# Washer_Control_Board.net
KiCad netlist of a schematic drawn in EAGLE
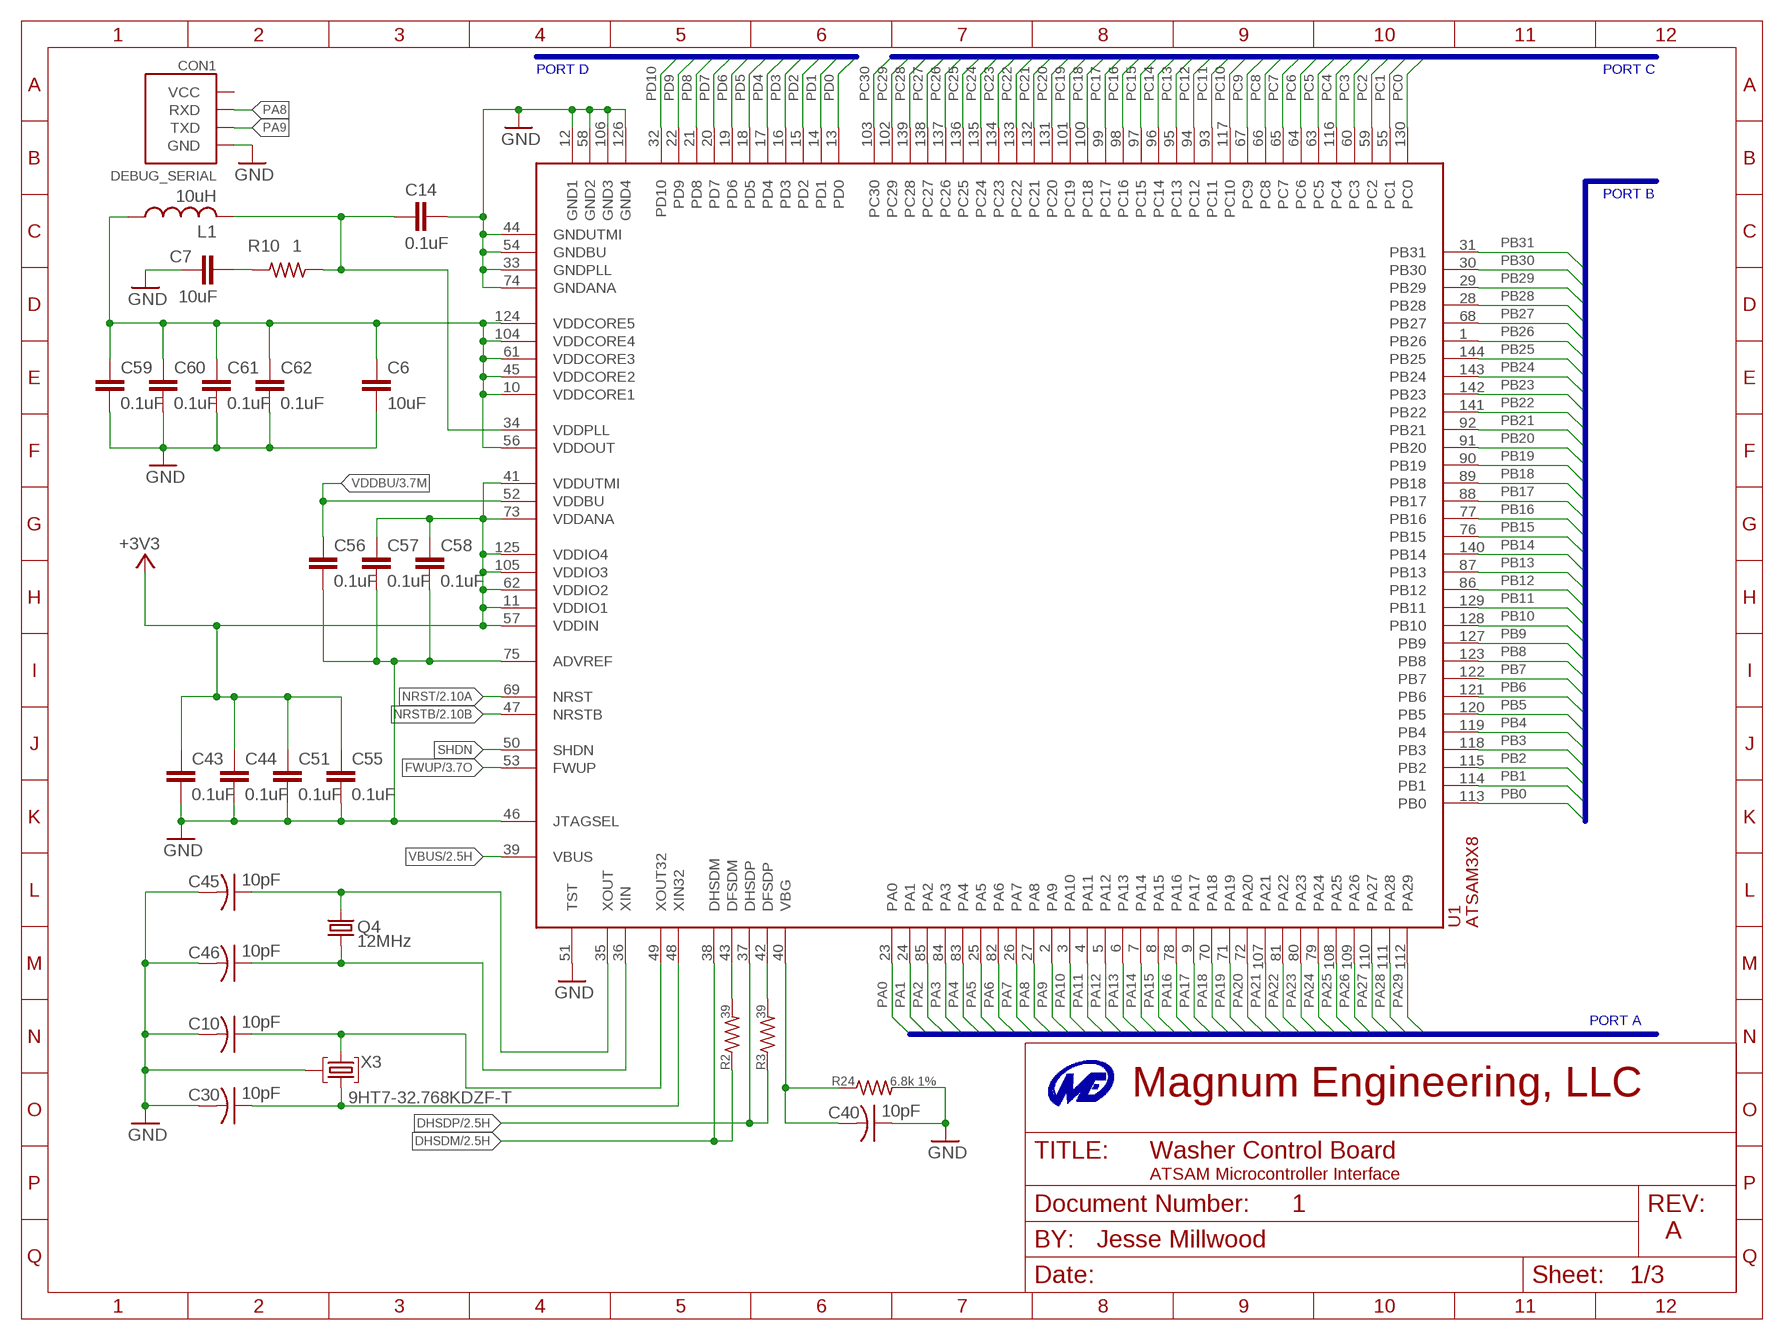
[diagram p0: schematic, sheet 1]
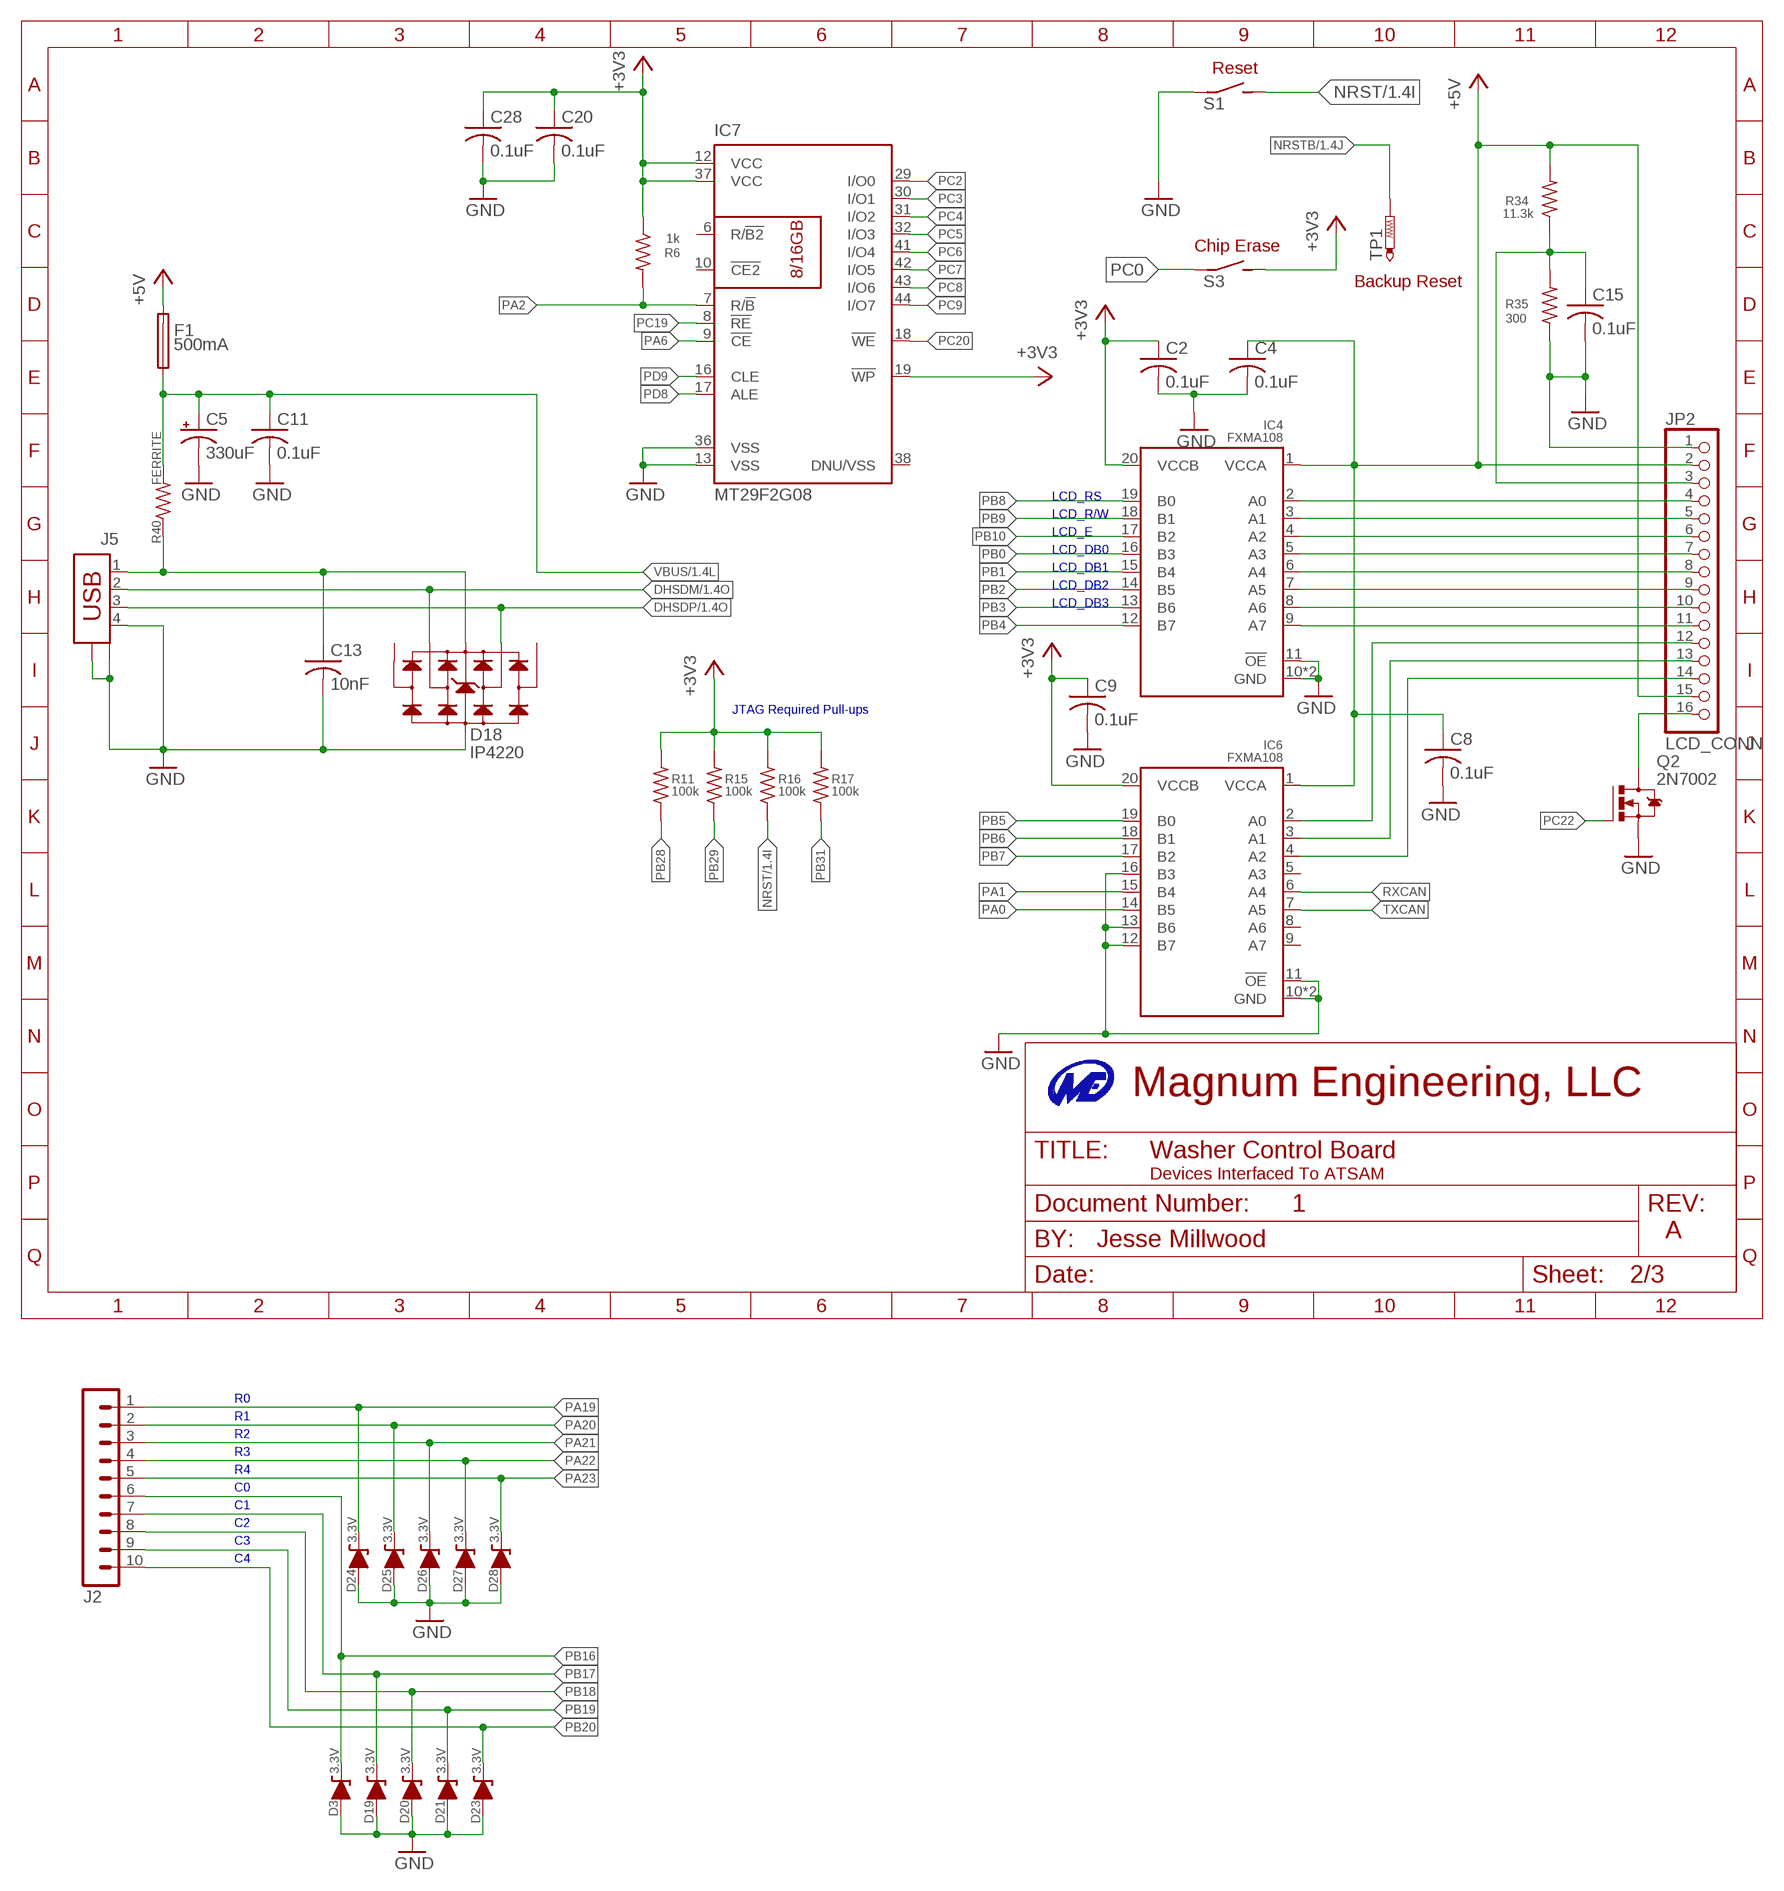
[diagram p1: schematic, sheet 2]
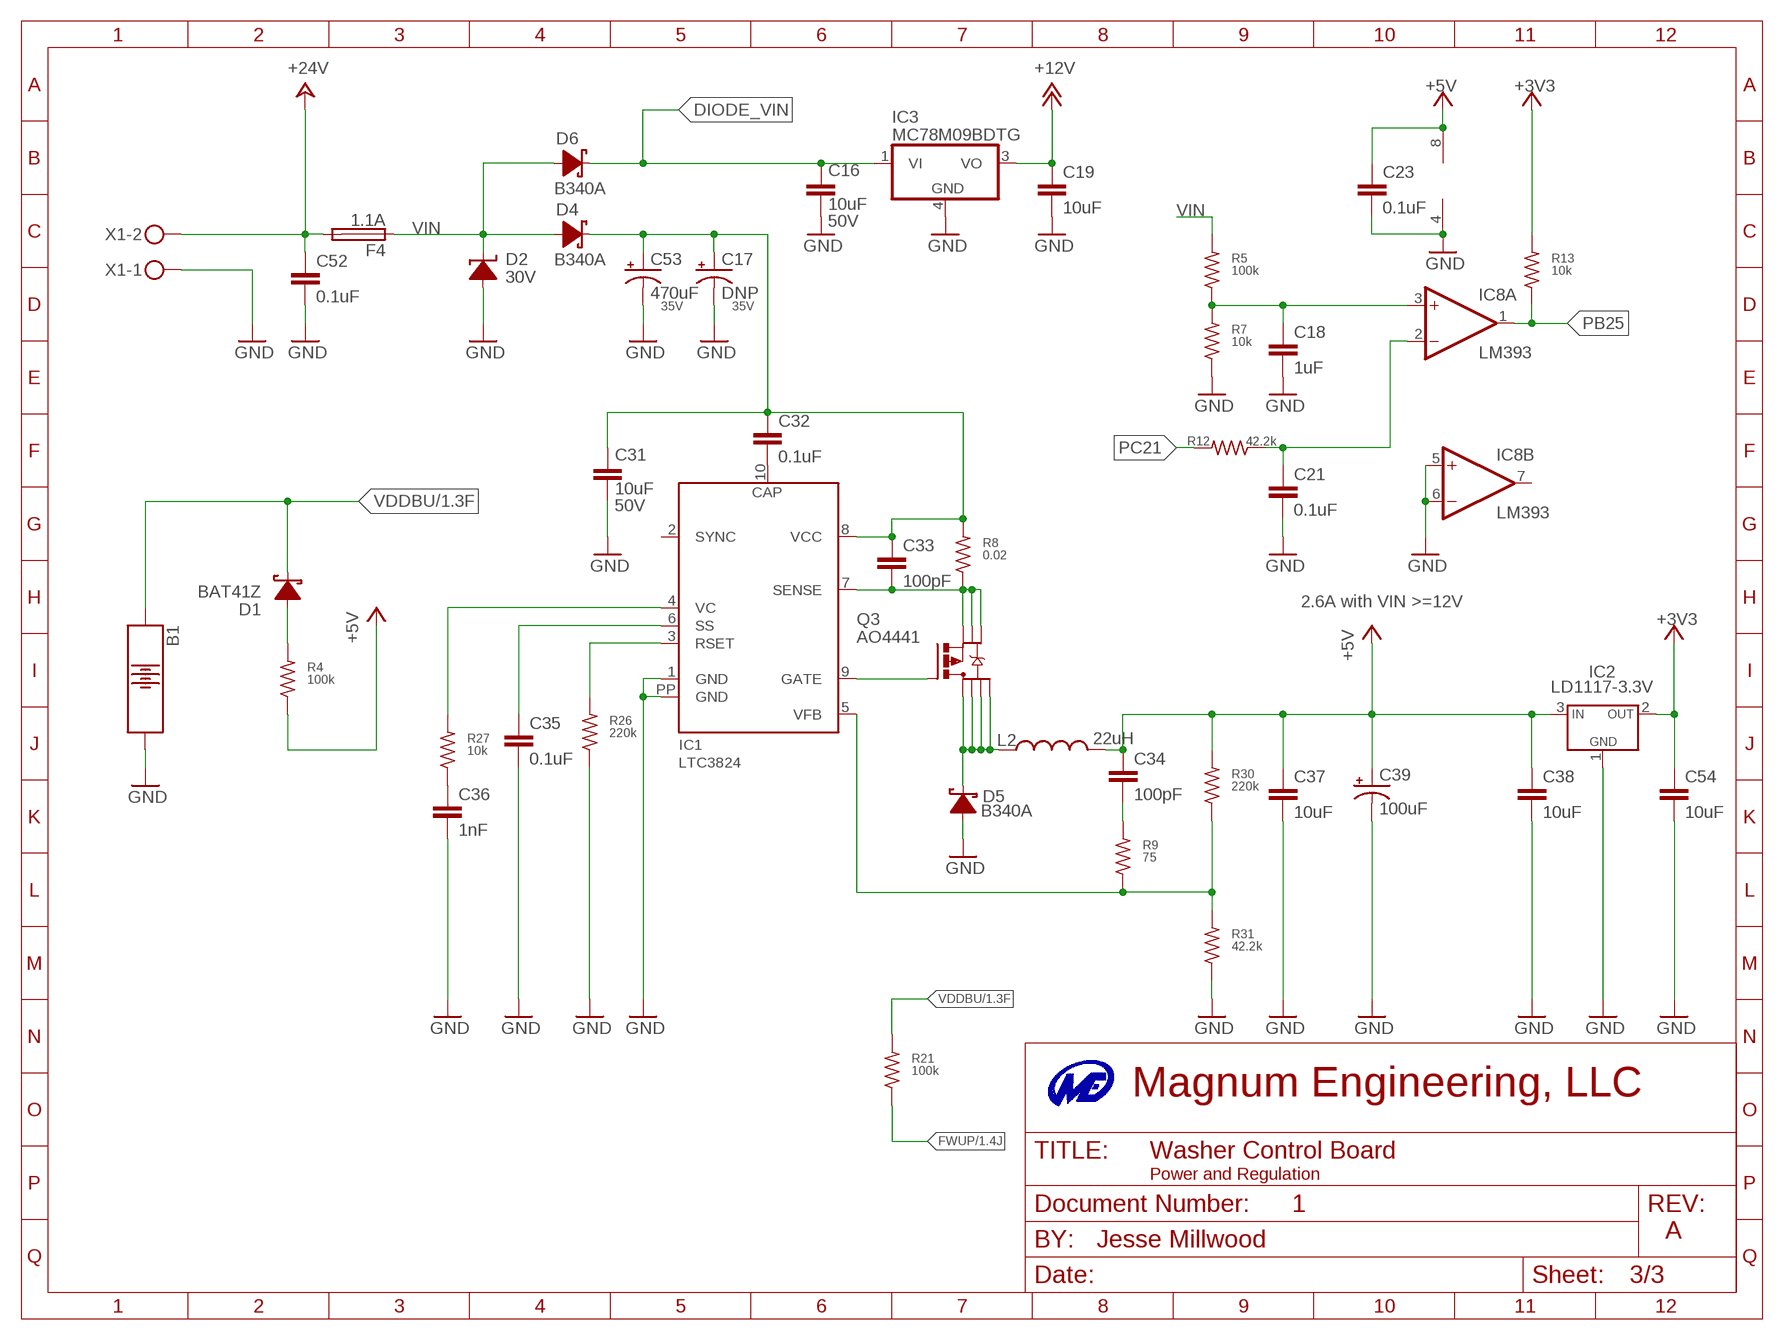
[diagram p2: schematic, sheet 3]

(export (version "E")
  (design (tool "Eeschema 10.0.6"))
  (components
    (comp (ref "C6")
      (value "10uF")
      (footprint "eagle-import:C0805")
      (libsource (lib "eagle-import") (part "C-EUC0805"))
    )
    (comp (ref "C7")
      (value "10uF")
      (footprint "eagle-import:C0805")
      (libsource (lib "eagle-import") (part "C-EUC0805"))
    )
    (comp (ref "C10")
      (value "10pF")
      (footprint "eagle-import:C0805")
      (libsource (lib "eagle-import") (part "CAPACITOR0805"))
    )
    (comp (ref "C14")
      (value "0.1uF")
      (footprint "eagle-import:C0805")
      (libsource (lib "eagle-import") (part "C-EUC0805"))
    )
    (comp (ref "C30")
      (value "10pF")
      (footprint "eagle-import:C0805")
      (libsource (lib "eagle-import") (part "CAPACITOR0805"))
    )
    (comp (ref "C40")
      (value "10pF")
      (footprint "eagle-import:C0805")
      (libsource (lib "eagle-import") (part "CAPACITOR0805"))
    )
    (comp (ref "C43")
      (value "0.1uF")
      (footprint "eagle-import:C0805")
      (libsource (lib "eagle-import") (part "C-EUC0805"))
    )
    (comp (ref "C44")
      (value "0.1uF")
      (footprint "eagle-import:C0805")
      (libsource (lib "eagle-import") (part "C-EUC0805"))
    )
    (comp (ref "C45")
      (value "10pF")
      (footprint "eagle-import:C0805")
      (libsource (lib "eagle-import") (part "CAPACITOR0805"))
    )
    (comp (ref "C46")
      (value "10pF")
      (footprint "eagle-import:C0805")
      (libsource (lib "eagle-import") (part "CAPACITOR0805"))
    )
    (comp (ref "C51")
      (value "0.1uF")
      (footprint "eagle-import:C0805")
      (libsource (lib "eagle-import") (part "C-EUC0805"))
    )
    (comp (ref "C55")
      (value "0.1uF")
      (footprint "eagle-import:C0805")
      (libsource (lib "eagle-import") (part "C-EUC0805"))
    )
    (comp (ref "C56")
      (value "0.1uF")
      (footprint "eagle-import:C0805")
      (libsource (lib "eagle-import") (part "C-EUC0805"))
    )
    (comp (ref "C57")
      (value "0.1uF")
      (footprint "eagle-import:C0805")
      (libsource (lib "eagle-import") (part "C-EUC0805"))
    )
    (comp (ref "C58")
      (value "0.1uF")
      (footprint "eagle-import:C0805")
      (libsource (lib "eagle-import") (part "C-EUC0805"))
    )
    (comp (ref "C59")
      (value "0.1uF")
      (footprint "eagle-import:C0805")
      (libsource (lib "eagle-import") (part "C-EUC0805"))
    )
    (comp (ref "C60")
      (value "0.1uF")
      (footprint "eagle-import:C0805")
      (libsource (lib "eagle-import") (part "C-EUC0805"))
    )
    (comp (ref "C61")
      (value "0.1uF")
      (footprint "eagle-import:C0805")
      (libsource (lib "eagle-import") (part "C-EUC0805"))
    )
    (comp (ref "C62")
      (value "0.1uF")
      (footprint "eagle-import:C0805")
      (libsource (lib "eagle-import") (part "C-EUC0805"))
    )
    (comp (ref "CON1")
      (value "DEBUG_SERIAL")
      (footprint "eagle-import:VIDEO_PARTS_DEBUG_SERIAL")
      (libsource (lib "eagle-import") (part "VIDEO_PARTS_DEBUG_SERIAL"))
    )
    (comp (ref "L1")
      (value "10uH")
      (footprint "eagle-import:L2012C")
      (libsource (lib "eagle-import") (part "rcl_L-USL2012C"))
    )
    (comp (ref "Q4")
      (value "12MHz")
      (footprint "eagle-import:HC49UP")
      (libsource (lib "eagle-import") (part "CRYSTALHC49UP"))
    )
    (comp (ref "R2")
      (value "39")
      (footprint "eagle-import:R0805")
      (libsource (lib "eagle-import") (part "RESISTOR0805"))
    )
    (comp (ref "R3")
      (value "39")
      (footprint "eagle-import:R0805")
      (libsource (lib "eagle-import") (part "RESISTOR0805"))
    )
    (comp (ref "R10")
      (value "1")
      (footprint "eagle-import:R0805")
      (libsource (lib "eagle-import") (part "R-US_R0805"))
    )
    (comp (ref "R24")
      (value "6.8k 1%")
      (footprint "eagle-import:R0805")
      (libsource (lib "eagle-import") (part "RESISTOR0805"))
    )
    (comp (ref "U1")
      (value "ATSAM3X8")
      (footprint "eagle-import:SMARTPRJ_LQFP144")
      (libsource (lib "eagle-import") (part "SMARTPRJ_ATSAM3X/AAU"))
    )
    (comp (ref "X3")
      (value "9HT7-32.768KDZF-T")
      (footprint "eagle-import:TXC-9HT7")
      (libsource (lib "eagle-import") (part "CRYSTAL"))
    )
    (comp (ref "C2")
      (value "0.1uF")
      (footprint "eagle-import:C0805")
      (libsource (lib "eagle-import") (part "CAPACITOR0805"))
    )
    (comp (ref "C4")
      (value "0.1uF")
      (footprint "eagle-import:C0805")
      (libsource (lib "eagle-import") (part "CAPACITOR0805"))
    )
    (comp (ref "C5")
      (value "330uF")
      (footprint "eagle-import:E2,5-6")
      (libsource (lib "eagle-import") (part "CPOL-USE2.5-6"))
    )
    (comp (ref "C8")
      (value "0.1uF")
      (footprint "eagle-import:C0805")
      (libsource (lib "eagle-import") (part "CAPACITOR0805"))
    )
    (comp (ref "C9")
      (value "0.1uF")
      (footprint "eagle-import:C0805")
      (libsource (lib "eagle-import") (part "CAPACITOR0805"))
    )
    (comp (ref "C11")
      (value "0.1uF")
      (footprint "eagle-import:C0805")
      (libsource (lib "eagle-import") (part "CAPACITOR0805"))
    )
    (comp (ref "C13")
      (value "10nF")
      (footprint "eagle-import:C0805")
      (libsource (lib "eagle-import") (part "CAPACITOR0805"))
    )
    (comp (ref "C15")
      (value "0.1uF")
      (footprint "eagle-import:C0805")
      (libsource (lib "eagle-import") (part "CAPACITOR0805"))
    )
    (comp (ref "C20")
      (value "0.1uF")
      (footprint "eagle-import:C0805")
      (libsource (lib "eagle-import") (part "CAPACITOR0805"))
    )
    (comp (ref "C28")
      (value "0.1uF")
      (footprint "eagle-import:C0805")
      (libsource (lib "eagle-import") (part "CAPACITOR0805"))
    )
    (comp (ref "D3")
      (value "3.3V")
      (footprint "eagle-import:SOT-23")
      (libsource (lib "eagle-import") (part "ZENERSOT-23"))
    )
    (comp (ref "D18")
      (value "IP4220")
      (footprint "eagle-import:SOT-23-6")
      (libsource (lib "eagle-import") (part "IP4220"))
    )
    (comp (ref "D19")
      (value "3.3V")
      (footprint "eagle-import:SOT-23")
      (libsource (lib "eagle-import") (part "ZENERSOT-23"))
    )
    (comp (ref "D20")
      (value "3.3V")
      (footprint "eagle-import:SOT-23")
      (libsource (lib "eagle-import") (part "ZENERSOT-23"))
    )
    (comp (ref "D21")
      (value "3.3V")
      (footprint "eagle-import:SOT-23")
      (libsource (lib "eagle-import") (part "ZENERSOT-23"))
    )
    (comp (ref "D23")
      (value "3.3V")
      (footprint "eagle-import:SOT-23")
      (libsource (lib "eagle-import") (part "ZENERSOT-23"))
    )
    (comp (ref "D24")
      (value "3.3V")
      (footprint "eagle-import:SOT-23")
      (libsource (lib "eagle-import") (part "ZENERSOT-23"))
    )
    (comp (ref "D25")
      (value "3.3V")
      (footprint "eagle-import:SOT-23")
      (libsource (lib "eagle-import") (part "ZENERSOT-23"))
    )
    (comp (ref "D26")
      (value "3.3V")
      (footprint "eagle-import:SOT-23")
      (libsource (lib "eagle-import") (part "ZENERSOT-23"))
    )
    (comp (ref "D27")
      (value "3.3V")
      (footprint "eagle-import:SOT-23")
      (libsource (lib "eagle-import") (part "ZENERSOT-23"))
    )
    (comp (ref "D28")
      (value "3.3V")
      (footprint "eagle-import:SOT-23")
      (libsource (lib "eagle-import") (part "ZENERSOT-23"))
    )
    (comp (ref "F1")
      (value "500mA")
      (footprint "eagle-import:LITTELFUSE1812")
      (libsource (lib "eagle-import") (part "ads4_FUSELITTELFUSE1812"))
    )
    (comp (ref "IC4")
      (value "FXMA108")
      (footprint "eagle-import:20DQFN")
      (libsource (lib "eagle-import") (part "FXMA108"))
    )
    (comp (ref "IC6")
      (value "FXMA108")
      (footprint "eagle-import:20DQFN")
      (libsource (lib "eagle-import") (part "FXMA108"))
    )
    (comp (ref "IC7")
      (value "MT29F2G08")
      (footprint "eagle-import:TSOP48")
      (libsource (lib "eagle-import") (part "MT29F8G08DAA"))
    )
    (comp (ref "J2")
      (value "MA10-152271")
      (footprint "eagle-import:52271-1069")
      (libsource (lib "eagle-import") (part "MA10-152271"))
    )
    (comp (ref "J5")
      (value "USB-787616")
      (footprint "eagle-import:USB")
      (libsource (lib "eagle-import") (part "USB-787616"))
    )
    (comp (ref "JP2")
      (value "LCD_CONN")
      (footprint "eagle-import:1X16")
      (libsource (lib "eagle-import") (part "PINHD-1X16"))
    )
    (comp (ref "Q2")
      (value "2N7002")
      (footprint "eagle-import:SOT-23")
      (libsource (lib "eagle-import") (part "2N7002"))
    )
    (comp (ref "R6")
      (value "1k")
      (footprint "eagle-import:R0805")
      (libsource (lib "eagle-import") (part "R-US_R0805"))
    )
    (comp (ref "R11")
      (value "100k")
      (footprint "eagle-import:R0805")
      (libsource (lib "eagle-import") (part "RESISTOR0805"))
    )
    (comp (ref "R15")
      (value "100k")
      (footprint "eagle-import:R0805")
      (libsource (lib "eagle-import") (part "RESISTOR0805"))
    )
    (comp (ref "R16")
      (value "100k")
      (footprint "eagle-import:R0805")
      (libsource (lib "eagle-import") (part "RESISTOR0805"))
    )
    (comp (ref "R17")
      (value "100k")
      (footprint "eagle-import:R0805")
      (libsource (lib "eagle-import") (part "RESISTOR0805"))
    )
    (comp (ref "R34")
      (value "11.3k")
      (footprint "eagle-import:R0805")
      (libsource (lib "eagle-import") (part "R-US_R0805"))
    )
    (comp (ref "R35")
      (value "300")
      (footprint "eagle-import:R0805")
      (libsource (lib "eagle-import") (part "R-US_R0805"))
    )
    (comp (ref "R40")
      (value "FERRITE")
      (footprint "eagle-import:R0805")
      (libsource (lib "eagle-import") (part "RESISTOR0805"))
    )
    (comp (ref "S1")
      (value "Reset")
      (footprint "eagle-import:EVQPJ")
      (libsource (lib "eagle-import") (part "SPST2EVQPJ"))
    )
    (comp (ref "S3")
      (value "Chip Erase")
      (footprint "eagle-import:EVQPJ")
      (libsource (lib "eagle-import") (part "SPST2EVQPJ"))
    )
    (comp (ref "TP1")
      (value "PTR1TP06R")
      (footprint "eagle-import:TP06R")
      (libsource (lib "eagle-import") (part "PTR1TP06R"))
    )
    (comp (ref "B1")
      (value "BS-7-ND")
      (footprint "eagle-import:BS-7-BATTERY-HOLDER")
      (libsource (lib "eagle-import") (part "BS-7-ND"))
    )
    (comp (ref "C16")
      (value "10uF")
      (footprint "eagle-import:C1206")
      (fields (field (name "VOLTAGE") "50V"))
      (libsource (lib "eagle-import") (part "C-EUC1206"))
    )
    (comp (ref "C17")
      (value "DNP")
      (footprint "eagle-import:RCL_E5-10,5")
      (fields (field (name "VOLTAGE") "35V"))
      (libsource (lib "eagle-import") (part "POL-CAPACITOR5-10.5"))
    )
    (comp (ref "C18")
      (value "1uF")
      (footprint "eagle-import:C0805")
      (libsource (lib "eagle-import") (part "C-EUC0805"))
    )
    (comp (ref "C19")
      (value "10uF")
      (footprint "eagle-import:C0805")
      (libsource (lib "eagle-import") (part "C-EUC0805"))
    )
    (comp (ref "C21")
      (value "0.1uF")
      (footprint "eagle-import:C0805")
      (libsource (lib "eagle-import") (part "C-EUC0805"))
    )
    (comp (ref "C23")
      (value "0.1uF")
      (footprint "eagle-import:C0805")
      (libsource (lib "eagle-import") (part "C-EUC0805"))
    )
    (comp (ref "C31")
      (value "10uF")
      (footprint "eagle-import:C1206")
      (fields (field (name "VOLTAGE") "50V"))
      (libsource (lib "eagle-import") (part "C-EUC1206"))
    )
    (comp (ref "C32")
      (value "0.1uF")
      (footprint "eagle-import:C0805")
      (libsource (lib "eagle-import") (part "C-EUC0805"))
    )
    (comp (ref "C33")
      (value "100pF")
      (footprint "eagle-import:C0805")
      (libsource (lib "eagle-import") (part "C-EUC0805"))
    )
    (comp (ref "C34")
      (value "100pF")
      (footprint "eagle-import:C0805")
      (libsource (lib "eagle-import") (part "C-EUC0805"))
    )
    (comp (ref "C35")
      (value "0.1uF")
      (footprint "eagle-import:C0805")
      (libsource (lib "eagle-import") (part "C-EUC0805"))
    )
    (comp (ref "C36")
      (value "1nF")
      (footprint "eagle-import:C0805")
      (libsource (lib "eagle-import") (part "C-EUC0805"))
    )
    (comp (ref "C37")
      (value "10uF")
      (footprint "eagle-import:C0805")
      (libsource (lib "eagle-import") (part "C-EUC0805"))
    )
    (comp (ref "C38")
      (value "10uF")
      (footprint "eagle-import:C0805")
      (libsource (lib "eagle-import") (part "C-EUC0805"))
    )
    (comp (ref "C39")
      (value "100uF")
      (footprint "eagle-import:RCL_E2-5")
      (libsource (lib "eagle-import") (part "POL-CAPACITOR2-5"))
    )
    (comp (ref "C52")
      (value "0.1uF")
      (footprint "eagle-import:C0805")
      (libsource (lib "eagle-import") (part "C-EUC0805"))
    )
    (comp (ref "C53")
      (value "470uF")
      (footprint "eagle-import:RCL_E5-10,5")
      (fields (field (name "VOLTAGE") "35V"))
      (libsource (lib "eagle-import") (part "POL-CAPACITOR5-10.5"))
    )
    (comp (ref "C54")
      (value "10uF")
      (footprint "eagle-import:C0805")
      (libsource (lib "eagle-import") (part "C-EUC0805"))
    )
    (comp (ref "D1")
      (value "BAT41Z")
      (footprint "eagle-import:SOD123@1")
      (fields (field (name "LEAKAGE") "Ileak=100nA"))
      (libsource (lib "eagle-import") (part "ads4_DIODE-SCHOTTKYSOD123"))
    )
    (comp (ref "D2")
      (value "30V")
      (footprint "eagle-import:SMA@2")
      (libsource (lib "eagle-import") (part "TVSSMA"))
    )
    (comp (ref "D4")
      (value "B340A")
      (footprint "eagle-import:SMA")
      (libsource (lib "eagle-import") (part "DIODE-SCHOTTKYSMA"))
    )
    (comp (ref "D5")
      (value "B340A")
      (footprint "eagle-import:SMA@1")
      (libsource (lib "eagle-import") (part "ads4_DIODE-SCHOTTKYSMA"))
    )
    (comp (ref "D6")
      (value "B340A")
      (footprint "eagle-import:SMA")
      (libsource (lib "eagle-import") (part "DIODE-SCHOTTKYSMA"))
    )
    (comp (ref "F4")
      (value "1.1A")
      (footprint "eagle-import:LITTELFUSE1812")
      (libsource (lib "eagle-import") (part "FUSELITTELFUSE1812"))
    )
    (comp (ref "IC1")
      (value "LTC3824")
      (footprint "eagle-import:MSOP10-PPPP")
      (libsource (lib "eagle-import") (part "LTC3824"))
    )
    (comp (ref "IC2")
      (value "LD1117-3.3V")
      (footprint "eagle-import:DPAK")
      (libsource (lib "eagle-import") (part "VREGLD1117-XX"))
    )
    (comp (ref "IC3")
      (value "MC78M09BDTG")
      (footprint "eagle-import:DPACK_3")
      (libsource (lib "eagle-import") (part "MC78M09BDTG"))
    )
    (comp (ref "IC8")
      (value "LM393")
      (footprint "eagle-import:SO-08")
      (libsource (lib "eagle-import") (part "LM293"))
    )
    (comp (ref "L2")
      (value "22uH")
      (footprint "eagle-import:SRR1280")
      (libsource (lib "eagle-import") (part "L-USSRR1280"))
    )
    (comp (ref "Q3")
      (value "AO4441")
      (footprint "eagle-import:SO8.MOSFETN")
      (libsource (lib "eagle-import") (part "MOSFET-P-SO8"))
    )
    (comp (ref "R4")
      (value "100k")
      (footprint "eagle-import:R0805")
      (libsource (lib "eagle-import") (part "RESISTOR0805"))
    )
    (comp (ref "R5")
      (value "100k")
      (footprint "eagle-import:R0805")
      (libsource (lib "eagle-import") (part "RESISTOR0805"))
    )
    (comp (ref "R7")
      (value "10k")
      (footprint "eagle-import:R0805")
      (libsource (lib "eagle-import") (part "RESISTOR0805"))
    )
    (comp (ref "R8")
      (value "0.02")
      (footprint "eagle-import:R0805")
      (libsource (lib "eagle-import") (part "RESISTOR0805"))
    )
    (comp (ref "R9")
      (value "75")
      (footprint "eagle-import:R0805")
      (libsource (lib "eagle-import") (part "RESISTOR0805"))
    )
    (comp (ref "R12")
      (value "42.2k")
      (footprint "eagle-import:R0805")
      (libsource (lib "eagle-import") (part "RESISTOR0805"))
    )
    (comp (ref "R13")
      (value "10k")
      (footprint "eagle-import:R0805")
      (libsource (lib "eagle-import") (part "RESISTOR0805"))
    )
    (comp (ref "R21")
      (value "100k")
      (footprint "eagle-import:R0805")
      (libsource (lib "eagle-import") (part "RESISTOR0805"))
    )
    (comp (ref "R26")
      (value "220k")
      (footprint "eagle-import:R0805")
      (libsource (lib "eagle-import") (part "RESISTOR0805"))
    )
    (comp (ref "R27")
      (value "10k")
      (footprint "eagle-import:R0805")
      (libsource (lib "eagle-import") (part "RESISTOR0805"))
    )
    (comp (ref "R30")
      (value "220k")
      (footprint "eagle-import:R0805")
      (libsource (lib "eagle-import") (part "RESISTOR0805"))
    )
    (comp (ref "R31")
      (value "42.2k")
      (footprint "eagle-import:R0805")
      (libsource (lib "eagle-import") (part "RESISTOR0805"))
    )
    (comp (ref "X1")
      (value "MKDSN1,5/2-5,08")
      (footprint "eagle-import:MKDSN1,5_2-5,08")
      (fields (field (name "MPN") "MKDSN 1,5/2-5.08"))
      (libsource (lib "eagle-import") (part "MKDSN1,5/2-5,08"))
    )
  )
  (nets
    (net (code "1") (name "+3V3") (class "Default")
      (node (ref "C2") (pin "1") (pinfunction "1_1") (pintype "passive"))
      (node (ref "C20") (pin "1") (pinfunction "1_1") (pintype "passive"))
      (node (ref "C28") (pin "1") (pinfunction "1_1") (pintype "passive"))
      (node (ref "C43") (pin "1") (pinfunction "1_1") (pintype "passive"))
      (node (ref "C44") (pin "1") (pinfunction "1_1") (pintype "passive"))
      (node (ref "C51") (pin "1") (pinfunction "1_1") (pintype "passive"))
      (node (ref "C54") (pin "1") (pinfunction "1_1") (pintype "passive"))
      (node (ref "C55") (pin "1") (pinfunction "1_1") (pintype "passive"))
      (node (ref "C57") (pin "1") (pinfunction "1_1") (pintype "passive"))
      (node (ref "C58") (pin "1") (pinfunction "1_1") (pintype "passive"))
      (node (ref "C9") (pin "1") (pinfunction "1_1") (pintype "passive"))
      (node (ref "IC2") (pin "2") (pinfunction "OUT_2") (pintype "passive"))
      (node (ref "IC4") (pin "20") (pinfunction "VCCB_20") (pintype "bidirectional"))
      (node (ref "IC6") (pin "20") (pinfunction "VCCB_20") (pintype "bidirectional"))
      (node (ref "IC7") (pin "12") (pinfunction "VCC_12") (pintype "power_in"))
      (node (ref "IC7") (pin "19") (pinfunction "~{WP}_19") (pintype "input"))
      (node (ref "IC7") (pin "37") (pinfunction "VCC_37") (pintype "power_in"))
      (node (ref "R11") (pin "2") (pinfunction "2_2") (pintype "passive"))
      (node (ref "R13") (pin "2") (pinfunction "2_2") (pintype "passive"))
      (node (ref "R15") (pin "2") (pinfunction "2_2") (pintype "passive"))
      (node (ref "R16") (pin "2") (pinfunction "2_2") (pintype "passive"))
      (node (ref "R17") (pin "2") (pinfunction "2_2") (pintype "passive"))
      (node (ref "R6") (pin "1") (pinfunction "1_1") (pintype "passive"))
      (node (ref "S3") (pin "B") (pinfunction "2_B") (pintype "passive"))
      (node (ref "U1") (pin "105") (pinfunction "VDDIO3_105") (pintype "power_in"))
      (node (ref "U1") (pin "11") (pinfunction "VDDIO1_11") (pintype "power_in"))
      (node (ref "U1") (pin "125") (pinfunction "VDDIO4_125") (pintype "power_in"))
      (node (ref "U1") (pin "41") (pinfunction "VDDUTMI_41") (pintype "input"))
      (node (ref "U1") (pin "57") (pinfunction "VDDIN_57") (pintype "power_in"))
      (node (ref "U1") (pin "62") (pinfunction "VDDIO2_62") (pintype "power_in"))
      (node (ref "U1") (pin "73") (pinfunction "VDDANA_73") (pintype "power_in"))
    )
    (net (code "2") (name "+5V") (class "Default")
      (node (ref "C23") (pin "1") (pinfunction "1_1") (pintype "passive"))
      (node (ref "C34") (pin "1") (pinfunction "1_1") (pintype "passive"))
      (node (ref "C37") (pin "1") (pinfunction "1_1") (pintype "passive"))
      (node (ref "C38") (pin "1") (pinfunction "1_1") (pintype "passive"))
      (node (ref "C39") (pin "+") (pinfunction "+_+") (pintype "passive"))
      (node (ref "C4") (pin "1") (pinfunction "1_1") (pintype "passive"))
      (node (ref "C8") (pin "1") (pinfunction "1_1") (pintype "passive"))
      (node (ref "F1") (pin "P$2") (pinfunction "2_P$2") (pintype "passive"))
      (node (ref "IC2") (pin "3") (pinfunction "IN_3") (pintype "passive"))
      (node (ref "IC4") (pin "1") (pinfunction "VCCA_1") (pintype "bidirectional"))
      (node (ref "IC6") (pin "1") (pinfunction "VCCA_1") (pintype "bidirectional"))
      (node (ref "IC8") (pin "8") (pinfunction "V+_8") (pintype "power_in"))
      (node (ref "JP2") (pin "15") (pinfunction "15_15") (pintype "passive"))
      (node (ref "JP2") (pin "2") (pinfunction "2_2") (pintype "passive"))
      (node (ref "L2") (pin "P$2") (pinfunction "2_P$2") (pintype "passive"))
      (node (ref "R30") (pin "2") (pinfunction "2_2") (pintype "passive"))
      (node (ref "R34") (pin "2") (pinfunction "2_2") (pintype "passive"))
      (node (ref "R4") (pin "1") (pinfunction "1_1") (pintype "passive"))
    )
    (net (code "3") (name "+12V") (class "Default")
      (node (ref "C19") (pin "1") (pinfunction "1_1") (pintype "passive"))
      (node (ref "IC3") (pin "3") (pinfunction "VO_3") (pintype "passive"))
    )
    (net (code "4") (name "+24V") (class "Default")
      (node (ref "C52") (pin "1") (pinfunction "1_1") (pintype "passive"))
      (node (ref "F4") (pin "P$2") (pinfunction "2_P$2") (pintype "passive"))
      (node (ref "X1") (pin "2") (pinfunction "KL_2") (pintype "passive"))
    )
    (net (code "5") (name "DHSDM") (class "Default")
      (node (ref "D18") (pin "6") (pinfunction "6_6") (pintype "passive"))
      (node (ref "J5") (pin "2") (pinfunction "2_2") (pintype "passive"))
      (node (ref "R2") (pin "1") (pinfunction "1_1") (pintype "passive"))
      (node (ref "U1") (pin "38") (pinfunction "DHSDM_38") (pintype "bidirectional"))
    )
    (net (code "6") (name "DHSDP") (class "Default")
      (node (ref "D18") (pin "4") (pinfunction "4_4") (pintype "passive"))
      (node (ref "J5") (pin "3") (pinfunction "3_3") (pintype "passive"))
      (node (ref "R3") (pin "1") (pinfunction "1_1") (pintype "passive"))
      (node (ref "U1") (pin "37") (pinfunction "DHSDP_37") (pintype "bidirectional"))
    )
    (net (code "7") (name "DIODE_VIN") (class "Default")
      (node (ref "C16") (pin "1") (pinfunction "1_1") (pintype "passive"))
      (node (ref "D6") (pin "C") (pinfunction "C_C") (pintype "passive"))
      (node (ref "IC3") (pin "1") (pinfunction "VI_1") (pintype "input"))
    )
    (net (code "8") (name "FWUP") (class "Default")
      (node (ref "R21") (pin "1") (pinfunction "1_1") (pintype "passive"))
      (node (ref "U1") (pin "53") (pinfunction "FWUP_53") (pintype "input"))
    )
    (net (code "9") (name "GND") (class "Default")
      (node (ref "B1") (pin "-") (pinfunction "B-_-") (pintype "power_in"))
      (node (ref "C10") (pin "2") (pinfunction "2_2") (pintype "passive"))
      (node (ref "C11") (pin "2") (pinfunction "2_2") (pintype "passive"))
      (node (ref "C13") (pin "2") (pinfunction "2_2") (pintype "passive"))
      (node (ref "C14") (pin "2") (pinfunction "2_2") (pintype "passive"))
      (node (ref "C15") (pin "2") (pinfunction "2_2") (pintype "passive"))
      (node (ref "C16") (pin "2") (pinfunction "2_2") (pintype "passive"))
      (node (ref "C17") (pin "-") (pinfunction "-_-") (pintype "passive"))
      (node (ref "C18") (pin "2") (pinfunction "2_2") (pintype "passive"))
      (node (ref "C19") (pin "2") (pinfunction "2_2") (pintype "passive"))
      (node (ref "C2") (pin "2") (pinfunction "2_2") (pintype "passive"))
      (node (ref "C20") (pin "2") (pinfunction "2_2") (pintype "passive"))
      (node (ref "C21") (pin "2") (pinfunction "2_2") (pintype "passive"))
      (node (ref "C23") (pin "2") (pinfunction "2_2") (pintype "passive"))
      (node (ref "C28") (pin "2") (pinfunction "2_2") (pintype "passive"))
      (node (ref "C30") (pin "2") (pinfunction "2_2") (pintype "passive"))
      (node (ref "C31") (pin "2") (pinfunction "2_2") (pintype "passive"))
      (node (ref "C35") (pin "2") (pinfunction "2_2") (pintype "passive"))
      (node (ref "C36") (pin "2") (pinfunction "2_2") (pintype "passive"))
      (node (ref "C37") (pin "2") (pinfunction "2_2") (pintype "passive"))
      (node (ref "C38") (pin "2") (pinfunction "2_2") (pintype "passive"))
      (node (ref "C39") (pin "-") (pinfunction "-_-") (pintype "passive"))
      (node (ref "C4") (pin "2") (pinfunction "2_2") (pintype "passive"))
      (node (ref "C40") (pin "1") (pinfunction "1_1") (pintype "passive"))
      (node (ref "C43") (pin "2") (pinfunction "2_2") (pintype "passive"))
      (node (ref "C44") (pin "2") (pinfunction "2_2") (pintype "passive"))
      (node (ref "C45") (pin "2") (pinfunction "2_2") (pintype "passive"))
      (node (ref "C46") (pin "2") (pinfunction "2_2") (pintype "passive"))
      (node (ref "C5") (pin "-") (pinfunction "-_-") (pintype "passive"))
      (node (ref "C51") (pin "2") (pinfunction "2_2") (pintype "passive"))
      (node (ref "C52") (pin "2") (pinfunction "2_2") (pintype "passive"))
      (node (ref "C53") (pin "-") (pinfunction "-_-") (pintype "passive"))
      (node (ref "C54") (pin "2") (pinfunction "2_2") (pintype "passive"))
      (node (ref "C55") (pin "2") (pinfunction "2_2") (pintype "passive"))
      (node (ref "C56") (pin "2") (pinfunction "2_2") (pintype "passive"))
      (node (ref "C57") (pin "2") (pinfunction "2_2") (pintype "passive"))
      (node (ref "C58") (pin "2") (pinfunction "2_2") (pintype "passive"))
      (node (ref "C59") (pin "2") (pinfunction "2_2") (pintype "passive"))
      (node (ref "C6") (pin "2") (pinfunction "2_2") (pintype "passive"))
      (node (ref "C60") (pin "2") (pinfunction "2_2") (pintype "passive"))
      (node (ref "C61") (pin "2") (pinfunction "2_2") (pintype "passive"))
      (node (ref "C62") (pin "2") (pinfunction "2_2") (pintype "passive"))
      (node (ref "C7") (pin "1") (pinfunction "1_1") (pintype "passive"))
      (node (ref "C8") (pin "2") (pinfunction "2_2") (pintype "passive"))
      (node (ref "C9") (pin "2") (pinfunction "2_2") (pintype "passive"))
      (node (ref "CON1") (pin "GND") (pinfunction "GND_GND") (pintype "passive"))
      (node (ref "D18") (pin "2") (pinfunction "GND_2") (pintype "passive"))
      (node (ref "D19") (pin "1") (pinfunction "A_1") (pintype "passive"))
      (node (ref "D2") (pin "A") (pinfunction "A_A") (pintype "passive"))
      (node (ref "D20") (pin "1") (pinfunction "A_1") (pintype "passive"))
      (node (ref "D21") (pin "1") (pinfunction "A_1") (pintype "passive"))
      (node (ref "D23") (pin "1") (pinfunction "A_1") (pintype "passive"))
      (node (ref "D24") (pin "1") (pinfunction "A_1") (pintype "passive"))
      (node (ref "D25") (pin "1") (pinfunction "A_1") (pintype "passive"))
      (node (ref "D26") (pin "1") (pinfunction "A_1") (pintype "passive"))
      (node (ref "D27") (pin "1") (pinfunction "A_1") (pintype "passive"))
      (node (ref "D28") (pin "1") (pinfunction "A_1") (pintype "passive"))
      (node (ref "D3") (pin "1") (pinfunction "A_1") (pintype "passive"))
      (node (ref "D5") (pin "A") (pinfunction "A_A") (pintype "passive"))
      (node (ref "IC1") (pin "1") (pinfunction "GND_1") (pintype "passive"))
      (node (ref "IC1") (pin "PP") (pinfunction "GND_PP") (pintype "passive"))
      (node (ref "IC2") (pin "1") (pinfunction "GND_1") (pintype "passive"))
      (node (ref "IC3") (pin "4") (pinfunction "GND_4") (pintype "passive"))
      (node (ref "IC4") (pin "10") (pinfunction "GND_10") (pintype "bidirectional"))
      (node (ref "IC4") (pin "11") (pinfunction "~{OE}_11") (pintype "bidirectional"))
      (node (ref "IC4") (pin "PAD") (pinfunction "GND_PAD") (pintype "bidirectional"))
      (node (ref "IC6") (pin "10") (pinfunction "GND_10") (pintype "bidirectional"))
      (node (ref "IC6") (pin "11") (pinfunction "~{OE}_11") (pintype "bidirectional"))
      (node (ref "IC6") (pin "12") (pinfunction "B7_12") (pintype "bidirectional"))
      (node (ref "IC6") (pin "13") (pinfunction "B6_13") (pintype "bidirectional"))
      (node (ref "IC6") (pin "16") (pinfunction "B3_16") (pintype "bidirectional"))
      (node (ref "IC6") (pin "PAD") (pinfunction "GND_PAD") (pintype "bidirectional"))
      (node (ref "IC7") (pin "13") (pinfunction "VSS_13") (pintype "power_in"))
      (node (ref "IC7") (pin "36") (pinfunction "VSS_36") (pintype "power_in"))
      (node (ref "IC8") (pin "4") (pinfunction "V-_4") (pintype "power_in"))
      (node (ref "IC8") (pin "5") (pinfunction "+IN_5") (pintype "input"))
      (node (ref "IC8") (pin "6") (pinfunction "-IN_6") (pintype "input"))
      (node (ref "J5") (pin "4") (pinfunction "4_4") (pintype "passive"))
      (node (ref "J5") (pin "P$1") (pinfunction "P$1_P$1") (pintype "bidirectional"))
      (node (ref "J5") (pin "P$2") (pinfunction "P$2_P$2") (pintype "bidirectional"))
      (node (ref "JP2") (pin "1") (pinfunction "1_1") (pintype "passive"))
      (node (ref "Q2") (pin "2") (pinfunction "S_2") (pintype "passive"))
      (node (ref "R24") (pin "2") (pinfunction "2_2") (pintype "passive"))
      (node (ref "R26") (pin "1") (pinfunction "1_1") (pintype "passive"))
      (node (ref "R31") (pin "1") (pinfunction "1_1") (pintype "passive"))
      (node (ref "R35") (pin "1") (pinfunction "1_1") (pintype "passive"))
      (node (ref "R7") (pin "1") (pinfunction "1_1") (pintype "passive"))
      (node (ref "S1") (pin "A") (pinfunction "1_A") (pintype "passive"))
      (node (ref "U1") (pin "106") (pinfunction "GND3_106") (pintype "power_in"))
      (node (ref "U1") (pin "12") (pinfunction "GND1_12") (pintype "power_in"))
      (node (ref "U1") (pin "126") (pinfunction "GND4_126") (pintype "power_in"))
      (node (ref "U1") (pin "33") (pinfunction "GNDPLL_33") (pintype "power_in"))
      (node (ref "U1") (pin "44") (pinfunction "GNDUTMI_44") (pintype "power_in"))
      (node (ref "U1") (pin "46") (pinfunction "JTAGSEL_46") (pintype "input"))
      (node (ref "U1") (pin "51") (pinfunction "TST_51") (pintype "input"))
      (node (ref "U1") (pin "54") (pinfunction "GNDBU_54") (pintype "power_in"))
      (node (ref "U1") (pin "58") (pinfunction "GND2_58") (pintype "power_in"))
      (node (ref "U1") (pin "74") (pinfunction "GNDANA_74") (pintype "power_in"))
      (node (ref "U1") (pin "75") (pinfunction "ADVREF_75") (pintype "power_in"))
      (node (ref "X1") (pin "1") (pinfunction "KL_1") (pintype "passive"))
      (node (ref "X3") (pin "2") (pinfunction "GND_2") (pintype "passive"))
      (node (ref "X3") (pin "3") (pinfunction "GND_3") (pintype "passive"))
    )
    (net (code "10") (name "NRST") (class "Default")
      (node (ref "R16") (pin "1") (pinfunction "1_1") (pintype "passive"))
      (node (ref "S1") (pin "B") (pinfunction "2_B") (pintype "passive"))
      (node (ref "U1") (pin "69") (pinfunction "NRST_69") (pintype "bidirectional"))
    )
    (net (code "11") (name "NRSTB") (class "Default")
      (node (ref "TP1") (pin "TP") (pinfunction "TP_TP") (pintype "input"))
      (node (ref "U1") (pin "47") (pinfunction "NRSTB_47") (pintype "input"))
    )
    (net (code "12") (name "Net-(C7-Pad2)") (class "Default")
      (node (ref "C7") (pin "2") (pinfunction "2_2") (pintype "passive"))
      (node (ref "R10") (pin "2") (pinfunction "2_2") (pintype "passive"))
    )
    (net (code "13") (name "Net-(C15-Pad1)") (class "Default")
      (node (ref "C15") (pin "1") (pinfunction "1_1") (pintype "passive"))
      (node (ref "JP2") (pin "3") (pinfunction "3_3") (pintype "passive"))
      (node (ref "R34") (pin "1") (pinfunction "1_1") (pintype "passive"))
      (node (ref "R35") (pin "2") (pinfunction "2_2") (pintype "passive"))
    )
    (net (code "14") (name "Net-(C34-Pad2)") (class "Default")
      (node (ref "C34") (pin "2") (pinfunction "2_2") (pintype "passive"))
      (node (ref "R9") (pin "2") (pinfunction "2_2") (pintype "passive"))
    )
    (net (code "15") (name "Net-(C36-Pad1)") (class "Default")
      (node (ref "C36") (pin "1") (pinfunction "1_1") (pintype "passive"))
      (node (ref "R27") (pin "1") (pinfunction "1_1") (pintype "passive"))
    )
    (net (code "16") (name "Net-(D1-PadA)") (class "Default")
      (node (ref "D1") (pin "A") (pinfunction "A_A") (pintype "passive"))
      (node (ref "R4") (pin "2") (pinfunction "2_2") (pintype "passive"))
    )
    (net (code "17") (name "Net-(D18-VBUS)") (class "Default")
      (node (ref "C13") (pin "1") (pinfunction "1_1") (pintype "passive"))
      (node (ref "D18") (pin "5") (pinfunction "VBUS_5") (pintype "passive"))
      (node (ref "J5") (pin "1") (pinfunction "1_1") (pintype "passive"))
      (node (ref "R40") (pin "1") (pinfunction "1_1") (pintype "passive"))
    )
    (net (code "18") (name "Net-(IC1-CAP)") (class "Default")
      (node (ref "C32") (pin "2") (pinfunction "2_2") (pintype "passive"))
      (node (ref "IC1") (pin "10") (pinfunction "CAP_10") (pintype "passive"))
    )
    (net (code "19") (name "Net-(IC1-GATE)") (class "Default")
      (node (ref "IC1") (pin "9") (pinfunction "GATE_9") (pintype "passive"))
      (node (ref "Q3") (pin "G") (pinfunction "G_G") (pintype "passive"))
    )
    (net (code "20") (name "Net-(IC1-RSET)") (class "Default")
      (node (ref "IC1") (pin "3") (pinfunction "RSET_3") (pintype "passive"))
      (node (ref "R26") (pin "2") (pinfunction "2_2") (pintype "passive"))
    )
    (net (code "21") (name "Net-(IC1-SENSE)") (class "Default")
      (node (ref "C33") (pin "2") (pinfunction "2_2") (pintype "passive"))
      (node (ref "IC1") (pin "7") (pinfunction "SENSE_7") (pintype "passive"))
      (node (ref "Q3") (pin "S$1") (pinfunction "S1_S$1") (pintype "passive"))
      (node (ref "Q3") (pin "S$2") (pinfunction "S2_S$2") (pintype "passive"))
      (node (ref "Q3") (pin "S$3") (pinfunction "S3_S$3") (pintype "passive"))
      (node (ref "R8") (pin "1") (pinfunction "1_1") (pintype "passive"))
    )
    (net (code "22") (name "Net-(IC1-SS)") (class "Default")
      (node (ref "C35") (pin "1") (pinfunction "1_1") (pintype "passive"))
      (node (ref "IC1") (pin "6") (pinfunction "SS_6") (pintype "passive"))
    )
    (net (code "23") (name "Net-(IC1-VC)") (class "Default")
      (node (ref "IC1") (pin "4") (pinfunction "VC_4") (pintype "passive"))
      (node (ref "R27") (pin "2") (pinfunction "2_2") (pintype "passive"))
    )
    (net (code "24") (name "Net-(IC1-VCC)") (class "Default")
      (node (ref "C17") (pin "+") (pinfunction "+_+") (pintype "passive"))
      (node (ref "C31") (pin "1") (pinfunction "1_1") (pintype "passive"))
      (node (ref "C32") (pin "1") (pinfunction "1_1") (pintype "passive"))
      (node (ref "C33") (pin "1") (pinfunction "1_1") (pintype "passive"))
      (node (ref "C53") (pin "+") (pinfunction "+_+") (pintype "passive"))
      (node (ref "D4") (pin "C") (pinfunction "C_C") (pintype "passive"))
      (node (ref "IC1") (pin "8") (pinfunction "VCC_8") (pintype "passive"))
      (node (ref "R8") (pin "2") (pinfunction "2_2") (pintype "passive"))
    )
    (net (code "25") (name "Net-(IC1-VFB)") (class "Default")
      (node (ref "IC1") (pin "5") (pinfunction "VFB_5") (pintype "passive"))
      (node (ref "R30") (pin "1") (pinfunction "1_1") (pintype "passive"))
      (node (ref "R31") (pin "2") (pinfunction "2_2") (pintype "passive"))
      (node (ref "R9") (pin "1") (pinfunction "1_1") (pintype "passive"))
    )
    (net (code "26") (name "Net-(IC4-A0)") (class "Default")
      (node (ref "IC4") (pin "2") (pinfunction "A0_2") (pintype "bidirectional"))
      (node (ref "JP2") (pin "4") (pinfunction "4_4") (pintype "passive"))
    )
    (net (code "27") (name "Net-(IC4-A1)") (class "Default")
      (node (ref "IC4") (pin "3") (pinfunction "A1_3") (pintype "bidirectional"))
      (node (ref "JP2") (pin "5") (pinfunction "5_5") (pintype "passive"))
    )
    (net (code "28") (name "Net-(IC4-A2)") (class "Default")
      (node (ref "IC4") (pin "4") (pinfunction "A2_4") (pintype "bidirectional"))
      (node (ref "JP2") (pin "6") (pinfunction "6_6") (pintype "passive"))
    )
    (net (code "29") (name "Net-(IC4-A3)") (class "Default")
      (node (ref "IC4") (pin "5") (pinfunction "A3_5") (pintype "bidirectional"))
      (node (ref "JP2") (pin "7") (pinfunction "7_7") (pintype "passive"))
    )
    (net (code "30") (name "Net-(IC4-A4)") (class "Default")
      (node (ref "IC4") (pin "6") (pinfunction "A4_6") (pintype "bidirectional"))
      (node (ref "JP2") (pin "8") (pinfunction "8_8") (pintype "passive"))
    )
    (net (code "31") (name "Net-(IC4-A5)") (class "Default")
      (node (ref "IC4") (pin "7") (pinfunction "A5_7") (pintype "bidirectional"))
      (node (ref "JP2") (pin "9") (pinfunction "9_9") (pintype "passive"))
    )
    (net (code "32") (name "Net-(IC4-A6)") (class "Default")
      (node (ref "IC4") (pin "8") (pinfunction "A6_8") (pintype "bidirectional"))
      (node (ref "JP2") (pin "10") (pinfunction "10_10") (pintype "passive"))
    )
    (net (code "33") (name "Net-(IC4-A7)") (class "Default")
      (node (ref "IC4") (pin "9") (pinfunction "A7_9") (pintype "bidirectional"))
      (node (ref "JP2") (pin "11") (pinfunction "11_11") (pintype "passive"))
    )
    (net (code "34") (name "Net-(IC6-A0)") (class "Default")
      (node (ref "IC6") (pin "2") (pinfunction "A0_2") (pintype "bidirectional"))
      (node (ref "JP2") (pin "12") (pinfunction "12_12") (pintype "passive"))
    )
    (net (code "35") (name "Net-(IC6-A1)") (class "Default")
      (node (ref "IC6") (pin "3") (pinfunction "A1_3") (pintype "bidirectional"))
      (node (ref "JP2") (pin "13") (pinfunction "13_13") (pintype "passive"))
    )
    (net (code "36") (name "Net-(IC6-A2)") (class "Default")
      (node (ref "IC6") (pin "4") (pinfunction "A2_4") (pintype "bidirectional"))
      (node (ref "JP2") (pin "14") (pinfunction "14_14") (pintype "passive"))
    )
    (net (code "37") (name "Net-(IC8A-+IN)") (class "Default")
      (node (ref "C18") (pin "1") (pinfunction "1_1") (pintype "passive"))
      (node (ref "IC8") (pin "3") (pinfunction "+IN_3") (pintype "input"))
      (node (ref "R5") (pin "1") (pinfunction "1_1") (pintype "passive"))
      (node (ref "R7") (pin "2") (pinfunction "2_2") (pintype "passive"))
    )
    (net (code "38") (name "Net-(IC8A--IN)") (class "Default")
      (node (ref "C21") (pin "1") (pinfunction "1_1") (pintype "passive"))
      (node (ref "IC8") (pin "2") (pinfunction "-IN_2") (pintype "input"))
      (node (ref "R12") (pin "1") (pinfunction "1_1") (pintype "passive"))
    )
    (net (code "39") (name "Net-(L2-1)") (class "Default")
      (node (ref "D5") (pin "C") (pinfunction "C_C") (pintype "passive"))
      (node (ref "L2") (pin "P$1") (pinfunction "1_P$1") (pintype "passive"))
      (node (ref "Q3") (pin "D$1") (pinfunction "D1_D$1") (pintype "passive"))
      (node (ref "Q3") (pin "D$2") (pinfunction "D2_D$2") (pintype "passive"))
      (node (ref "Q3") (pin "D$3") (pinfunction "D3_D$3") (pintype "passive"))
      (node (ref "Q3") (pin "D$4") (pinfunction "D4_D$4") (pintype "passive"))
    )
    (net (code "40") (name "Net-(Q2-D)") (class "Default")
      (node (ref "JP2") (pin "16") (pinfunction "16_16") (pintype "passive"))
      (node (ref "Q2") (pin "3") (pinfunction "D_3") (pintype "passive"))
    )
    (net (code "41") (name "Net-(U1-DFSDM)") (class "Default")
      (node (ref "R2") (pin "2") (pinfunction "2_2") (pintype "passive"))
      (node (ref "U1") (pin "43") (pinfunction "DFSDM_43") (pintype "input"))
    )
    (net (code "42") (name "Net-(U1-DFSDP)") (class "Default")
      (node (ref "R3") (pin "2") (pinfunction "2_2") (pintype "passive"))
      (node (ref "U1") (pin "42") (pinfunction "DFSDP_42") (pintype "input"))
    )
    (net (code "43") (name "Net-(U1-VBG)") (class "Default")
      (node (ref "C40") (pin "2") (pinfunction "2_2") (pintype "passive"))
      (node (ref "R24") (pin "1") (pinfunction "1_1") (pintype "passive"))
      (node (ref "U1") (pin "40") (pinfunction "VBG_40") (pintype "passive"))
    )
    (net (code "44") (name "Net-(U1-VDDCORE1)") (class "Default")
      (node (ref "C59") (pin "1") (pinfunction "1_1") (pintype "passive"))
      (node (ref "C6") (pin "1") (pinfunction "1_1") (pintype "passive"))
      (node (ref "C60") (pin "1") (pinfunction "1_1") (pintype "passive"))
      (node (ref "C61") (pin "1") (pinfunction "1_1") (pintype "passive"))
      (node (ref "C62") (pin "1") (pinfunction "1_1") (pintype "passive"))
      (node (ref "L1") (pin "1") (pinfunction "1_1") (pintype "passive"))
      (node (ref "U1") (pin "10") (pinfunction "VDDCORE1_10") (pintype "input"))
      (node (ref "U1") (pin "104") (pinfunction "VDDCORE4_104") (pintype "input"))
      (node (ref "U1") (pin "124") (pinfunction "VDDCORE5_124") (pintype "input"))
      (node (ref "U1") (pin "45") (pinfunction "VDDCORE2_45") (pintype "input"))
      (node (ref "U1") (pin "56") (pinfunction "VDDOUT_56") (pintype "output"))
      (node (ref "U1") (pin "61") (pinfunction "VDDCORE3_61") (pintype "input"))
    )
    (net (code "45") (name "Net-(U1-VDDPLL)") (class "Default")
      (node (ref "C14") (pin "1") (pinfunction "1_1") (pintype "passive"))
      (node (ref "L1") (pin "2") (pinfunction "2_2") (pintype "passive"))
      (node (ref "R10") (pin "1") (pinfunction "1_1") (pintype "passive"))
      (node (ref "U1") (pin "34") (pinfunction "VDDPLL_34") (pintype "input"))
    )
    (net (code "46") (name "Net-(U1-XIN)") (class "Default")
      (node (ref "C46") (pin "1") (pinfunction "1_1") (pintype "passive"))
      (node (ref "Q4") (pin "1") (pinfunction "1_1") (pintype "passive"))
      (node (ref "U1") (pin "36") (pinfunction "XIN_36") (pintype "input"))
    )
    (net (code "47") (name "Net-(U1-XIN32)") (class "Default")
      (node (ref "C30") (pin "1") (pinfunction "1_1") (pintype "passive"))
      (node (ref "U1") (pin "48") (pinfunction "XIN32_48") (pintype "output"))
      (node (ref "X3") (pin "1") (pinfunction "X1_1") (pintype "passive"))
    )
    (net (code "48") (name "Net-(U1-XOUT)") (class "Default")
      (node (ref "C45") (pin "1") (pinfunction "1_1") (pintype "passive"))
      (node (ref "Q4") (pin "2") (pinfunction "2_2") (pintype "passive"))
      (node (ref "U1") (pin "35") (pinfunction "XOUT_35") (pintype "output"))
    )
    (net (code "49") (name "Net-(U1-XOUT32)") (class "Default")
      (node (ref "C10") (pin "1") (pinfunction "1_1") (pintype "passive"))
      (node (ref "U1") (pin "49") (pinfunction "XOUT32_49") (pintype "output"))
      (node (ref "X3") (pin "4") (pinfunction "X2_4") (pintype "passive"))
    )
    (net (code "50") (name "PA0") (class "Default")
      (node (ref "IC6") (pin "14") (pinfunction "B5_14") (pintype "bidirectional"))
      (node (ref "U1") (pin "23") (pinfunction "PA0_23") (pintype "bidirectional"))
    )
    (net (code "51") (name "PA1") (class "Default")
      (node (ref "IC6") (pin "15") (pinfunction "B4_15") (pintype "bidirectional"))
      (node (ref "U1") (pin "24") (pinfunction "PA1_24") (pintype "bidirectional"))
    )
    (net (code "52") (name "PA2") (class "Default")
      (node (ref "IC7") (pin "7") (pinfunction "R/~{B}_7") (pintype "input"))
      (node (ref "R6") (pin "2") (pinfunction "2_2") (pintype "passive"))
      (node (ref "U1") (pin "85") (pinfunction "PA2_85") (pintype "bidirectional"))
    )
    (net (code "53") (name "PA3") (class "Default")
      (node (ref "U1") (pin "84") (pinfunction "PA3_84") (pintype "bidirectional"))
    )
    (net (code "54") (name "PA4") (class "Default")
      (node (ref "U1") (pin "83") (pinfunction "PA4_83") (pintype "bidirectional"))
    )
    (net (code "55") (name "PA5") (class "Default")
      (node (ref "U1") (pin "25") (pinfunction "PA5_25") (pintype "bidirectional"))
    )
    (net (code "56") (name "PA6") (class "Default")
      (node (ref "IC7") (pin "9") (pinfunction "~{CE}_9") (pintype "input"))
      (node (ref "U1") (pin "82") (pinfunction "PA6_82") (pintype "bidirectional"))
    )
    (net (code "57") (name "PA7") (class "Default")
      (node (ref "U1") (pin "26") (pinfunction "PA7_26") (pintype "bidirectional"))
    )
    (net (code "58") (name "PA8") (class "Default")
      (node (ref "CON1") (pin "RXD") (pinfunction "RXD_RXD") (pintype "passive"))
      (node (ref "U1") (pin "27") (pinfunction "PA8_27") (pintype "bidirectional"))
    )
    (net (code "59") (name "PA9") (class "Default")
      (node (ref "CON1") (pin "TXD") (pinfunction "TXD_TXD") (pintype "passive"))
      (node (ref "U1") (pin "2") (pinfunction "PA9_2") (pintype "bidirectional"))
    )
    (net (code "60") (name "PA10") (class "Default")
      (node (ref "U1") (pin "3") (pinfunction "PA10_3") (pintype "bidirectional"))
    )
    (net (code "61") (name "PA11") (class "Default")
      (node (ref "U1") (pin "4") (pinfunction "PA11_4") (pintype "bidirectional"))
    )
    (net (code "62") (name "PA12") (class "Default")
      (node (ref "U1") (pin "5") (pinfunction "PA12_5") (pintype "bidirectional"))
    )
    (net (code "63") (name "PA13") (class "Default")
      (node (ref "U1") (pin "6") (pinfunction "PA13_6") (pintype "bidirectional"))
    )
    (net (code "64") (name "PA14") (class "Default")
      (node (ref "U1") (pin "7") (pinfunction "PA14_7") (pintype "bidirectional"))
    )
    (net (code "65") (name "PA15") (class "Default")
      (node (ref "U1") (pin "8") (pinfunction "PA15_8") (pintype "bidirectional"))
    )
    (net (code "66") (name "PA16") (class "Default")
      (node (ref "U1") (pin "78") (pinfunction "PA16_78") (pintype "bidirectional"))
    )
    (net (code "67") (name "PA17") (class "Default")
      (node (ref "U1") (pin "9") (pinfunction "PA17_9") (pintype "bidirectional"))
    )
    (net (code "68") (name "PA18") (class "Default")
      (node (ref "U1") (pin "70") (pinfunction "PA18_70") (pintype "bidirectional"))
    )
    (net (code "69") (name "PA19") (class "Default")
      (node (ref "D24") (pin "3") (pinfunction "K_3") (pintype "passive"))
      (node (ref "J2") (pin "1") (pinfunction "1_1") (pintype "passive"))
      (node (ref "U1") (pin "71") (pinfunction "PA19_71") (pintype "bidirectional"))
    )
    (net (code "70") (name "PA20") (class "Default")
      (node (ref "D25") (pin "3") (pinfunction "K_3") (pintype "passive"))
      (node (ref "J2") (pin "2") (pinfunction "2_2") (pintype "passive"))
      (node (ref "U1") (pin "72") (pinfunction "PA20_72") (pintype "bidirectional"))
    )
    (net (code "71") (name "PA21") (class "Default")
      (node (ref "D26") (pin "3") (pinfunction "K_3") (pintype "passive"))
      (node (ref "J2") (pin "3") (pinfunction "3_3") (pintype "passive"))
      (node (ref "U1") (pin "107") (pinfunction "PA21_107") (pintype "bidirectional"))
    )
    (net (code "72") (name "PA22") (class "Default")
      (node (ref "D27") (pin "3") (pinfunction "K_3") (pintype "passive"))
      (node (ref "J2") (pin "4") (pinfunction "4_4") (pintype "passive"))
      (node (ref "U1") (pin "81") (pinfunction "PA22_81") (pintype "bidirectional"))
    )
    (net (code "73") (name "PA23") (class "Default")
      (node (ref "D28") (pin "3") (pinfunction "K_3") (pintype "passive"))
      (node (ref "J2") (pin "5") (pinfunction "5_5") (pintype "passive"))
      (node (ref "U1") (pin "80") (pinfunction "PA23_80") (pintype "bidirectional"))
    )
    (net (code "74") (name "PA24") (class "Default")
      (node (ref "U1") (pin "79") (pinfunction "PA24_79") (pintype "bidirectional"))
    )
    (net (code "75") (name "PA25") (class "Default")
      (node (ref "U1") (pin "108") (pinfunction "PA25_108") (pintype "bidirectional"))
    )
    (net (code "76") (name "PA26") (class "Default")
      (node (ref "U1") (pin "109") (pinfunction "PA26_109") (pintype "bidirectional"))
    )
    (net (code "77") (name "PA27") (class "Default")
      (node (ref "U1") (pin "110") (pinfunction "PA27_110") (pintype "bidirectional"))
    )
    (net (code "78") (name "PA28") (class "Default")
      (node (ref "U1") (pin "111") (pinfunction "PA28_111") (pintype "bidirectional"))
    )
    (net (code "79") (name "PA29") (class "Default")
      (node (ref "U1") (pin "112") (pinfunction "PA29_112") (pintype "bidirectional"))
    )
    (net (code "80") (name "PB0") (class "Default")
      (node (ref "IC4") (pin "16") (pinfunction "B3_16") (pintype "bidirectional"))
      (node (ref "U1") (pin "113") (pinfunction "PB0_113") (pintype "bidirectional"))
    )
    (net (code "81") (name "PB1") (class "Default")
      (node (ref "IC4") (pin "15") (pinfunction "B4_15") (pintype "bidirectional"))
      (node (ref "U1") (pin "114") (pinfunction "PB1_114") (pintype "bidirectional"))
    )
    (net (code "82") (name "PB2") (class "Default")
      (node (ref "IC4") (pin "14") (pinfunction "B5_14") (pintype "bidirectional"))
      (node (ref "U1") (pin "115") (pinfunction "PB2_115") (pintype "bidirectional"))
    )
    (net (code "83") (name "PB3") (class "Default")
      (node (ref "IC4") (pin "13") (pinfunction "B6_13") (pintype "bidirectional"))
      (node (ref "U1") (pin "118") (pinfunction "PB3_118") (pintype "bidirectional"))
    )
    (net (code "84") (name "PB4") (class "Default")
      (node (ref "IC4") (pin "12") (pinfunction "B7_12") (pintype "bidirectional"))
      (node (ref "U1") (pin "119") (pinfunction "PB4_119") (pintype "bidirectional"))
    )
    (net (code "85") (name "PB5") (class "Default")
      (node (ref "IC6") (pin "19") (pinfunction "B0_19") (pintype "bidirectional"))
      (node (ref "U1") (pin "120") (pinfunction "PB5_120") (pintype "bidirectional"))
    )
    (net (code "86") (name "PB6") (class "Default")
      (node (ref "IC6") (pin "18") (pinfunction "B1_18") (pintype "bidirectional"))
      (node (ref "U1") (pin "121") (pinfunction "PB6_121") (pintype "bidirectional"))
    )
    (net (code "87") (name "PB7") (class "Default")
      (node (ref "IC6") (pin "17") (pinfunction "B2_17") (pintype "bidirectional"))
      (node (ref "U1") (pin "122") (pinfunction "PB7_122") (pintype "bidirectional"))
    )
    (net (code "88") (name "PB8") (class "Default")
      (node (ref "IC4") (pin "19") (pinfunction "B0_19") (pintype "bidirectional"))
      (node (ref "U1") (pin "123") (pinfunction "PB8_123") (pintype "bidirectional"))
    )
    (net (code "89") (name "PB9") (class "Default")
      (node (ref "IC4") (pin "18") (pinfunction "B1_18") (pintype "bidirectional"))
      (node (ref "U1") (pin "127") (pinfunction "PB9_127") (pintype "bidirectional"))
    )
    (net (code "90") (name "PB10") (class "Default")
      (node (ref "IC4") (pin "17") (pinfunction "B2_17") (pintype "bidirectional"))
      (node (ref "U1") (pin "128") (pinfunction "PB10_128") (pintype "bidirectional"))
    )
    (net (code "91") (name "PB11") (class "Default")
      (node (ref "U1") (pin "129") (pinfunction "PB11_129") (pintype "bidirectional"))
    )
    (net (code "92") (name "PB12") (class "Default")
      (node (ref "U1") (pin "86") (pinfunction "PB12_86") (pintype "bidirectional"))
    )
    (net (code "93") (name "PB13") (class "Default")
      (node (ref "U1") (pin "87") (pinfunction "PB13_87") (pintype "bidirectional"))
    )
    (net (code "94") (name "PB14") (class "Default")
      (node (ref "U1") (pin "140") (pinfunction "PB14_140") (pintype "bidirectional"))
    )
    (net (code "95") (name "PB15") (class "Default")
      (node (ref "U1") (pin "76") (pinfunction "PB15_76") (pintype "bidirectional"))
    )
    (net (code "96") (name "PB16") (class "Default")
      (node (ref "D3") (pin "3") (pinfunction "K_3") (pintype "passive"))
      (node (ref "J2") (pin "6") (pinfunction "6_6") (pintype "passive"))
      (node (ref "U1") (pin "77") (pinfunction "PB16_77") (pintype "bidirectional"))
    )
    (net (code "97") (name "PB17") (class "Default")
      (node (ref "D19") (pin "3") (pinfunction "K_3") (pintype "passive"))
      (node (ref "J2") (pin "7") (pinfunction "7_7") (pintype "passive"))
      (node (ref "U1") (pin "88") (pinfunction "PB17_88") (pintype "bidirectional"))
    )
    (net (code "98") (name "PB18") (class "Default")
      (node (ref "D20") (pin "3") (pinfunction "K_3") (pintype "passive"))
      (node (ref "J2") (pin "8") (pinfunction "8_8") (pintype "passive"))
      (node (ref "U1") (pin "89") (pinfunction "PB18_89") (pintype "bidirectional"))
    )
    (net (code "99") (name "PB19") (class "Default")
      (node (ref "D21") (pin "3") (pinfunction "K_3") (pintype "passive"))
      (node (ref "J2") (pin "9") (pinfunction "9_9") (pintype "passive"))
      (node (ref "U1") (pin "90") (pinfunction "PB19_90") (pintype "bidirectional"))
    )
    (net (code "100") (name "PB20") (class "Default")
      (node (ref "D23") (pin "3") (pinfunction "K_3") (pintype "passive"))
      (node (ref "J2") (pin "10") (pinfunction "10_10") (pintype "passive"))
      (node (ref "U1") (pin "91") (pinfunction "PB20_91") (pintype "bidirectional"))
    )
    (net (code "101") (name "PB21") (class "Default")
      (node (ref "U1") (pin "92") (pinfunction "PB21_92") (pintype "bidirectional"))
    )
    (net (code "102") (name "PB22") (class "Default")
      (node (ref "U1") (pin "141") (pinfunction "PB22_141") (pintype "bidirectional"))
    )
    (net (code "103") (name "PB23") (class "Default")
      (node (ref "U1") (pin "142") (pinfunction "PB23_142") (pintype "bidirectional"))
    )
    (net (code "104") (name "PB24") (class "Default")
      (node (ref "U1") (pin "143") (pinfunction "PB24_143") (pintype "bidirectional"))
    )
    (net (code "105") (name "PB25") (class "Default")
      (node (ref "IC8") (pin "1") (pinfunction "OUT_1") (pintype "output"))
      (node (ref "R13") (pin "1") (pinfunction "1_1") (pintype "passive"))
      (node (ref "U1") (pin "144") (pinfunction "PB25_144") (pintype "bidirectional"))
    )
    (net (code "106") (name "PB26") (class "Default")
      (node (ref "U1") (pin "1") (pinfunction "PB26_1") (pintype "bidirectional"))
    )
    (net (code "107") (name "PB27") (class "Default")
      (node (ref "U1") (pin "68") (pinfunction "PB27_68") (pintype "bidirectional"))
    )
    (net (code "108") (name "PB28") (class "Default")
      (node (ref "R11") (pin "1") (pinfunction "1_1") (pintype "passive"))
      (node (ref "U1") (pin "28") (pinfunction "PB28_28") (pintype "bidirectional"))
    )
    (net (code "109") (name "PB29") (class "Default")
      (node (ref "R15") (pin "1") (pinfunction "1_1") (pintype "passive"))
      (node (ref "U1") (pin "29") (pinfunction "PB29_29") (pintype "bidirectional"))
    )
    (net (code "110") (name "PB30") (class "Default")
      (node (ref "U1") (pin "30") (pinfunction "PB30_30") (pintype "bidirectional"))
    )
    (net (code "111") (name "PB31") (class "Default")
      (node (ref "R17") (pin "1") (pinfunction "1_1") (pintype "passive"))
      (node (ref "U1") (pin "31") (pinfunction "PB31_31") (pintype "bidirectional"))
    )
    (net (code "112") (name "PC0") (class "Default")
      (node (ref "S3") (pin "A") (pinfunction "1_A") (pintype "passive"))
      (node (ref "U1") (pin "130") (pinfunction "PC0_130") (pintype "bidirectional"))
    )
    (net (code "113") (name "PC1") (class "Default")
      (node (ref "U1") (pin "55") (pinfunction "PC1_55") (pintype "bidirectional"))
    )
    (net (code "114") (name "PC2") (class "Default")
      (node (ref "IC7") (pin "29") (pinfunction "I/O0_29") (pintype "bidirectional"))
      (node (ref "U1") (pin "59") (pinfunction "PC2_59") (pintype "bidirectional"))
    )
    (net (code "115") (name "PC3") (class "Default")
      (node (ref "IC7") (pin "30") (pinfunction "I/O1_30") (pintype "bidirectional"))
      (node (ref "U1") (pin "60") (pinfunction "PC3_60") (pintype "bidirectional"))
    )
    (net (code "116") (name "PC4") (class "Default")
      (node (ref "IC7") (pin "31") (pinfunction "I/O2_31") (pintype "bidirectional"))
      (node (ref "U1") (pin "116") (pinfunction "PC4_116") (pintype "bidirectional"))
    )
    (net (code "117") (name "PC5") (class "Default")
      (node (ref "IC7") (pin "32") (pinfunction "I/O3_32") (pintype "bidirectional"))
      (node (ref "U1") (pin "63") (pinfunction "PC5_63") (pintype "bidirectional"))
    )
    (net (code "118") (name "PC6") (class "Default")
      (node (ref "IC7") (pin "41") (pinfunction "I/O4_41") (pintype "bidirectional"))
      (node (ref "U1") (pin "64") (pinfunction "PC6_64") (pintype "bidirectional"))
    )
    (net (code "119") (name "PC7") (class "Default")
      (node (ref "IC7") (pin "42") (pinfunction "I/O5_42") (pintype "bidirectional"))
      (node (ref "U1") (pin "65") (pinfunction "PC7_65") (pintype "bidirectional"))
    )
    (net (code "120") (name "PC8") (class "Default")
      (node (ref "IC7") (pin "43") (pinfunction "I/O6_43") (pintype "bidirectional"))
      (node (ref "U1") (pin "66") (pinfunction "PC8_66") (pintype "bidirectional"))
    )
    (net (code "121") (name "PC9") (class "Default")
      (node (ref "IC7") (pin "44") (pinfunction "I/O7_44") (pintype "bidirectional"))
      (node (ref "U1") (pin "67") (pinfunction "PC9_67") (pintype "bidirectional"))
    )
    (net (code "122") (name "PC10") (class "Default")
      (node (ref "U1") (pin "117") (pinfunction "PC10_117") (pintype "bidirectional"))
    )
    (net (code "123") (name "PC11") (class "Default")
      (node (ref "U1") (pin "93") (pinfunction "PC11_93") (pintype "bidirectional"))
    )
    (net (code "124") (name "PC12") (class "Default")
      (node (ref "U1") (pin "94") (pinfunction "PC12_94") (pintype "bidirectional"))
    )
    (net (code "125") (name "PC13") (class "Default")
      (node (ref "U1") (pin "95") (pinfunction "PC13_95") (pintype "bidirectional"))
    )
    (net (code "126") (name "PC14") (class "Default")
      (node (ref "U1") (pin "96") (pinfunction "PC14_96") (pintype "bidirectional"))
    )
    (net (code "127") (name "PC15") (class "Default")
      (node (ref "U1") (pin "97") (pinfunction "PC15_97") (pintype "bidirectional"))
    )
    (net (code "128") (name "PC16") (class "Default")
      (node (ref "U1") (pin "98") (pinfunction "PC16_98") (pintype "bidirectional"))
    )
    (net (code "129") (name "PC17") (class "Default")
      (node (ref "U1") (pin "99") (pinfunction "PC17_99") (pintype "bidirectional"))
    )
    (net (code "130") (name "PC18") (class "Default")
      (node (ref "U1") (pin "100") (pinfunction "PC18_100") (pintype "bidirectional"))
    )
    (net (code "131") (name "PC19") (class "Default")
      (node (ref "IC7") (pin "8") (pinfunction "~{RE}_8") (pintype "input"))
      (node (ref "U1") (pin "101") (pinfunction "PC19_101") (pintype "bidirectional"))
    )
    (net (code "132") (name "PC20") (class "Default")
      (node (ref "IC7") (pin "18") (pinfunction "~{WE}_18") (pintype "input"))
      (node (ref "U1") (pin "131") (pinfunction "PC20_131") (pintype "bidirectional"))
    )
    (net (code "133") (name "PC21") (class "Default")
      (node (ref "R12") (pin "2") (pinfunction "2_2") (pintype "passive"))
      (node (ref "U1") (pin "132") (pinfunction "PC21_132") (pintype "bidirectional"))
    )
    (net (code "134") (name "PC22") (class "Default")
      (node (ref "Q2") (pin "1") (pinfunction "G_1") (pintype "passive"))
      (node (ref "U1") (pin "133") (pinfunction "PC22_133") (pintype "bidirectional"))
    )
    (net (code "135") (name "PC23") (class "Default")
      (node (ref "U1") (pin "134") (pinfunction "PC23_134") (pintype "bidirectional"))
    )
    (net (code "136") (name "PC24") (class "Default")
      (node (ref "U1") (pin "135") (pinfunction "PC24_135") (pintype "bidirectional"))
    )
    (net (code "137") (name "PC25") (class "Default")
      (node (ref "U1") (pin "136") (pinfunction "PC25_136") (pintype "bidirectional"))
    )
    (net (code "138") (name "PC26") (class "Default")
      (node (ref "U1") (pin "137") (pinfunction "PC26_137") (pintype "bidirectional"))
    )
    (net (code "139") (name "PC27") (class "Default")
      (node (ref "U1") (pin "138") (pinfunction "PC27_138") (pintype "bidirectional"))
    )
    (net (code "140") (name "PC28") (class "Default")
      (node (ref "U1") (pin "139") (pinfunction "PC28_139") (pintype "bidirectional"))
    )
    (net (code "141") (name "PC29") (class "Default")
      (node (ref "U1") (pin "102") (pinfunction "PC29_102") (pintype "bidirectional"))
    )
    (net (code "142") (name "PC30") (class "Default")
      (node (ref "U1") (pin "103") (pinfunction "PC30_103") (pintype "bidirectional"))
    )
    (net (code "143") (name "PD0") (class "Default")
      (node (ref "U1") (pin "13") (pinfunction "PD0_13") (pintype "bidirectional"))
    )
    (net (code "144") (name "PD1") (class "Default")
      (node (ref "U1") (pin "14") (pinfunction "PD1_14") (pintype "bidirectional"))
    )
    (net (code "145") (name "PD2") (class "Default")
      (node (ref "U1") (pin "15") (pinfunction "PD2_15") (pintype "bidirectional"))
    )
    (net (code "146") (name "PD3") (class "Default")
      (node (ref "U1") (pin "16") (pinfunction "PD3_16") (pintype "bidirectional"))
    )
    (net (code "147") (name "PD4") (class "Default")
      (node (ref "U1") (pin "17") (pinfunction "PD4_17") (pintype "bidirectional"))
    )
    (net (code "148") (name "PD5") (class "Default")
      (node (ref "U1") (pin "18") (pinfunction "PD5_18") (pintype "bidirectional"))
    )
    (net (code "149") (name "PD6") (class "Default")
      (node (ref "U1") (pin "19") (pinfunction "PD6_19") (pintype "bidirectional"))
    )
    (net (code "150") (name "PD7") (class "Default")
      (node (ref "U1") (pin "20") (pinfunction "PD7_20") (pintype "bidirectional"))
    )
    (net (code "151") (name "PD8") (class "Default")
      (node (ref "IC7") (pin "17") (pinfunction "ALE_17") (pintype "input"))
      (node (ref "U1") (pin "21") (pinfunction "PD8_21") (pintype "bidirectional"))
    )
    (net (code "152") (name "PD9") (class "Default")
      (node (ref "IC7") (pin "16") (pinfunction "CLE_16") (pintype "input"))
      (node (ref "U1") (pin "22") (pinfunction "PD9_22") (pintype "bidirectional"))
    )
    (net (code "153") (name "PD10") (class "Default")
      (node (ref "U1") (pin "32") (pinfunction "PD10_32") (pintype "bidirectional"))
    )
    (net (code "154") (name "RXCAN") (class "Default")
      (node (ref "IC6") (pin "6") (pinfunction "A4_6") (pintype "bidirectional"))
    )
    (net (code "155") (name "SHDN") (class "Default")
      (node (ref "U1") (pin "50") (pinfunction "SHDN_50") (pintype "output"))
    )
    (net (code "156") (name "TXCAN") (class "Default")
      (node (ref "IC6") (pin "7") (pinfunction "A5_7") (pintype "bidirectional"))
    )
    (net (code "157") (name "VBUS") (class "Default")
      (node (ref "C11") (pin "1") (pinfunction "1_1") (pintype "passive"))
      (node (ref "C5") (pin "+") (pinfunction "+_+") (pintype "passive"))
      (node (ref "F1") (pin "P$1") (pinfunction "1_P$1") (pintype "passive"))
      (node (ref "R40") (pin "2") (pinfunction "2_2") (pintype "passive"))
      (node (ref "U1") (pin "39") (pinfunction "VBUS_39") (pintype "power_in"))
    )
    (net (code "158") (name "VDDBU") (class "Default")
      (node (ref "B1") (pin "+") (pinfunction "B+_+") (pintype "power_in"))
      (node (ref "C56") (pin "1") (pinfunction "1_1") (pintype "passive"))
      (node (ref "D1") (pin "K") (pinfunction "C_K") (pintype "passive"))
      (node (ref "R21") (pin "2") (pinfunction "2_2") (pintype "passive"))
      (node (ref "U1") (pin "52") (pinfunction "VDDBU_52") (pintype "power_in"))
    )
    (net (code "159") (name "VIN") (class "Default")
      (node (ref "D2") (pin "C") (pinfunction "C_C") (pintype "passive"))
      (node (ref "D4") (pin "A") (pinfunction "A_A") (pintype "passive"))
      (node (ref "D6") (pin "A") (pinfunction "A_A") (pintype "passive"))
      (node (ref "F4") (pin "P$1") (pinfunction "1_P$1") (pintype "passive"))
      (node (ref "R5") (pin "2") (pinfunction "2_2") (pintype "passive"))
    )
    (net (code "160") (name "unconnected-(CON1-PadVCC)") (class "Default")
      (node (ref "CON1") (pin "VCC") (pinfunction "VCC_VCC") (pintype "passive"))
    )
    (net (code "161") (name "unconnected-(D18-Pad1)") (class "Default")
      (node (ref "D18") (pin "1") (pinfunction "1_1") (pintype "passive"))
    )
    (net (code "162") (name "unconnected-(D18-Pad3)") (class "Default")
      (node (ref "D18") (pin "3") (pinfunction "3_3") (pintype "passive"))
    )
    (net (code "163") (name "unconnected-(IC1-SYNC-Pad2)") (class "Default")
      (node (ref "IC1") (pin "2") (pinfunction "SYNC_2") (pintype "passive"))
    )
    (net (code "164") (name "unconnected-(IC6-A3-Pad5)") (class "Default")
      (node (ref "IC6") (pin "5") (pinfunction "A3_5") (pintype "bidirectional"))
    )
    (net (code "165") (name "unconnected-(IC6-A6-Pad8)") (class "Default")
      (node (ref "IC6") (pin "8") (pinfunction "A6_8") (pintype "bidirectional"))
    )
    (net (code "166") (name "unconnected-(IC6-A7-Pad9)") (class "Default")
      (node (ref "IC6") (pin "9") (pinfunction "A7_9") (pintype "bidirectional"))
    )
    (net (code "167") (name "unconnected-(IC7-DNU-Pad25)") (class "Default")
      (node (ref "IC7") (pin "25") (pinfunction "DNU_25") (pintype "no_connect"))
    )
    (net (code "168") (name "unconnected-(IC7-DNU-Pad26)") (class "Default")
      (node (ref "IC7") (pin "26") (pinfunction "DNU_26") (pintype "no_connect"))
    )
    (net (code "169") (name "unconnected-(IC7-DNU-Pad48)") (class "Default")
      (node (ref "IC7") (pin "48") (pinfunction "DNU_48") (pintype "no_connect"))
    )
    (net (code "170") (name "unconnected-(IC7-DNU{slash}VSS-Pad38)") (class "Default")
      (node (ref "IC7") (pin "38") (pinfunction "DNU/VSS_38") (pintype "passive"))
    )
    (net (code "171") (name "unconnected-(IC7-R{slash}~{B2}-Pad6)") (class "Default")
      (node (ref "IC7") (pin "6") (pinfunction "R/~{B2}_6") (pintype "passive"))
    )
    (net (code "172") (name "unconnected-(IC7-~{CE2}-Pad10)") (class "Default")
      (node (ref "IC7") (pin "10") (pinfunction "~{CE2}_10") (pintype "passive"))
    )
    (net (code "173") (name "unconnected-(IC8B-OUT-Pad7)") (class "Default")
      (node (ref "IC8") (pin "7") (pinfunction "OUT_7") (pintype "output"))
    )
  )
)
